# AUDIO2.net
KiCad netlist of a schematic drawn in Altium Designer
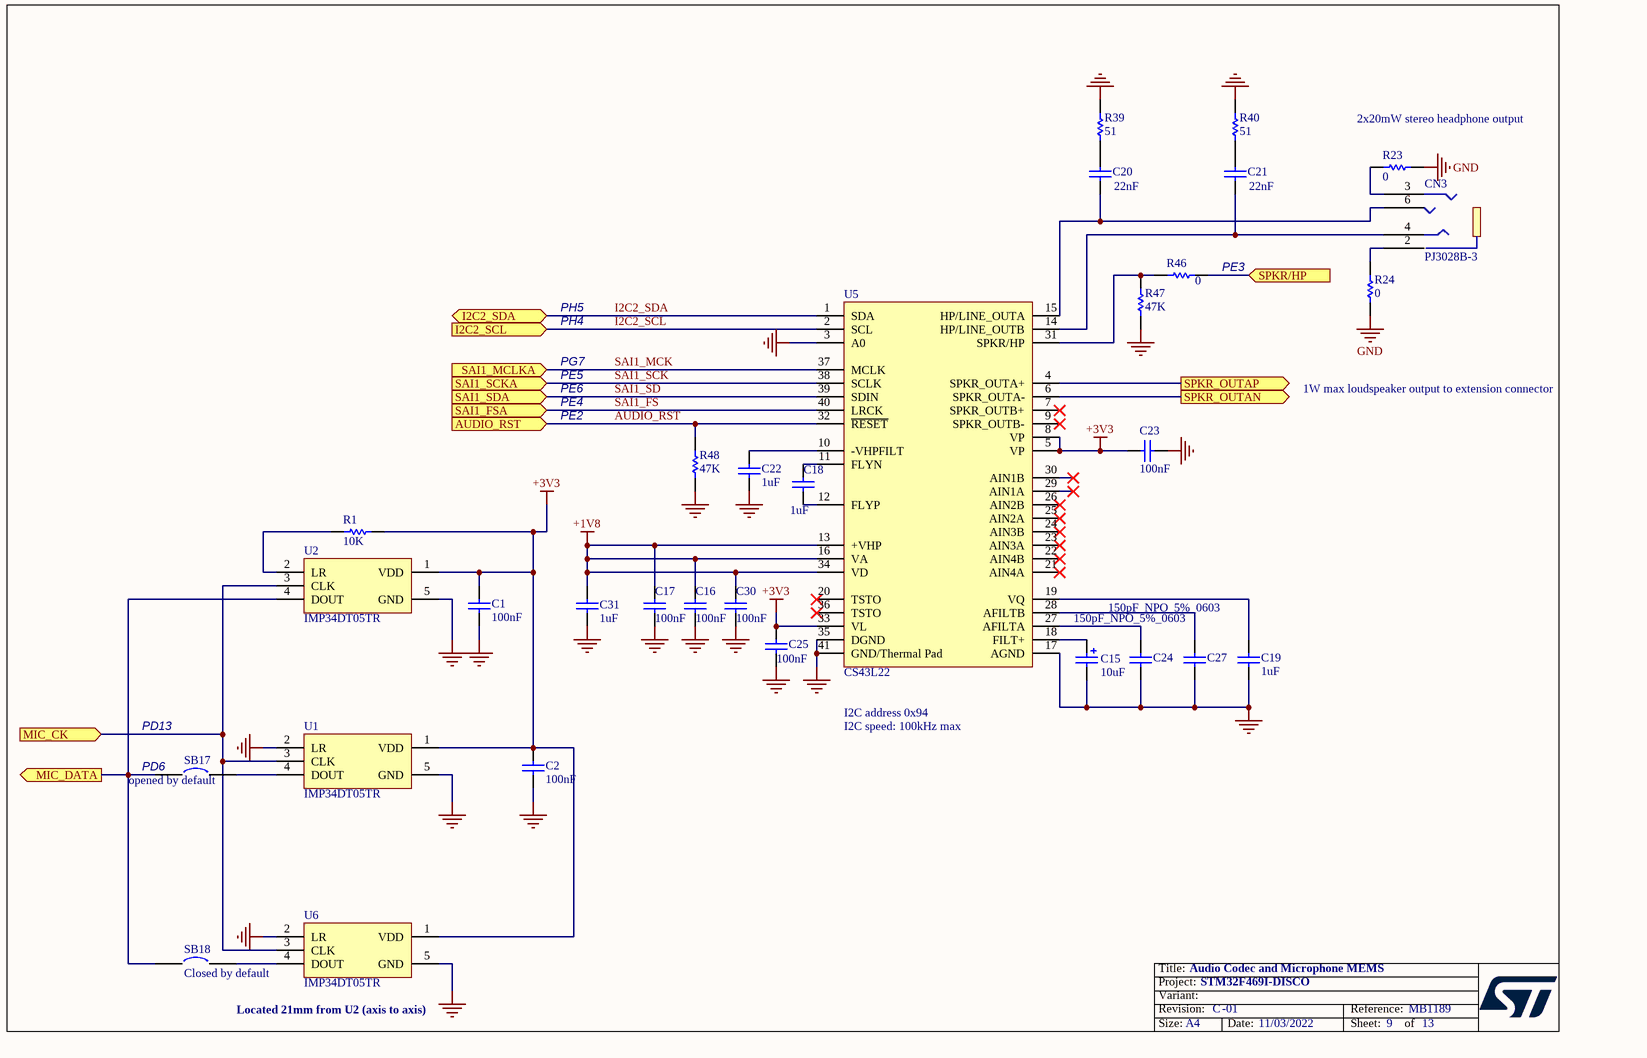
[diagram p0: AUDIO2.SchDoc]

(export (version "E")
  (design (tool "Eeschema 10.0.6"))
  (components
    (comp (ref "C1")
      (value "100nF")
      (footprint "0402C")
      (description "Capacitor")
      (fields (field (name "PUBLISHER") "Altium Limited"))
      (libsource (lib "Miscellaneous Devices") (part "Cap"))
    )
    (comp (ref "C2")
      (value "100nF")
      (footprint "0402C")
      (description "Capacitor")
      (fields (field (name "PUBLISHER") "Altium Limited"))
      (libsource (lib "Miscellaneous Devices") (part "Cap"))
    )
    (comp (ref "C15")
      (value "10uF")
      (footprint "CPOL_TAJ-A_1206_H180")
      (description "Capacitor, Tantalum, 10uF, 16V, 10%, 3Ohms, pkg Type_A (3216 metric), T=1.6mm")
      (libsource (lib "MB1189") (part "Cap_TAJA106K016R"))
    )
    (comp (ref "C16")
      (value "100nF")
      (footprint "0402C")
      (description "Capacitor")
      (fields (field (name "PUBLISHER") "Altium Limited"))
      (libsource (lib "Miscellaneous Devices") (part "CAP"))
    )
    (comp (ref "C17")
      (value "100nF")
      (footprint "0402C")
      (description "Capacitor")
      (fields (field (name "PUBLISHER") "Altium Limited"))
      (libsource (lib "Miscellaneous Devices") (part "CAP"))
    )
    (comp (ref "C18")
      (value "1uF")
      (footprint "0603C")
      (description "Capacitor")
      (fields (field (name "PUBLISHER") "Altium Limited"))
      (libsource (lib "Miscellaneous Devices") (part "CAP"))
    )
    (comp (ref "C19")
      (value "1uF")
      (footprint "0603C")
      (description "Capacitor")
      (fields (field (name "PUBLISHER") "Altium Limited"))
      (libsource (lib "Miscellaneous Devices") (part "CAP"))
    )
    (comp (ref "C20")
      (value "22nF")
      (footprint "0603C")
      (description "Capacitor,22nF,50V,X7R,10%,0603,YAGEO")
      (libsource (lib "MCD_TOOLS") (part "Cap_22nF_X7R_10%_0603"))
    )
    (comp (ref "C21")
      (value "22nF")
      (footprint "0603C")
      (description "Capacitor,22nF,50V,X7R,10%,0603,YAGEO")
      (libsource (lib "MCD_TOOLS") (part "Cap_22nF_X7R_10%_0603"))
    )
    (comp (ref "C22")
      (value "1uF")
      (footprint "0603C")
      (description "Capacitor")
      (fields (field (name "PUBLISHER") "Altium Limited"))
      (libsource (lib "Miscellaneous Devices") (part "CAP"))
    )
    (comp (ref "C23")
      (value "100nF")
      (footprint "0402C")
      (description "Capacitor")
      (fields (field (name "PUBLISHER") "Altium Limited"))
      (libsource (lib "Miscellaneous Devices") (part "CAP"))
    )
    (comp (ref "C24")
      (value "150pF_NPO_5%_0603")
      (footprint "0603C")
      (description "Capacitor,150pF,50V,NPO,5%,0603,YAGEO")
      (libsource (lib "MCD_TOOLS") (part "Cap_150pF_NPO_5%_0603"))
    )
    (comp (ref "C25")
      (value "100nF")
      (footprint "0402C")
      (description "Capacitor")
      (fields (field (name "PUBLISHER") "Altium Limited"))
      (libsource (lib "Miscellaneous Devices") (part "CAP"))
    )
    (comp (ref "C27")
      (value "150pF_NPO_5%_0603")
      (footprint "0603C")
      (description "Capacitor,150pF,50V,NPO,5%,0603,YAGEO")
      (libsource (lib "MCD_TOOLS") (part "Cap_150pF_NPO_5%_0603"))
    )
    (comp (ref "C30")
      (value "100nF")
      (footprint "0402C")
      (description "Capacitor")
      (fields (field (name "PUBLISHER") "Altium Limited"))
      (libsource (lib "Miscellaneous Devices") (part "CAP"))
    )
    (comp (ref "C31")
      (value "1uF")
      (footprint "0603C")
      (description "Capacitor")
      (fields (field (name "PUBLISHER") "Altium Limited"))
      (libsource (lib "Miscellaneous Devices") (part "CAP"))
    )
    (comp (ref "CN3") (value "PJ3028B-3") (footprint "PJ3028B") (libsource (lib "MB786") (part "PJ3028B-3")))
    (comp (ref "R1")
      (value "10K")
      (footprint "0603R")
      (description "Resistor")
      (libsource (lib "MCD_TOOLS") (part "Res_0_5%_0402"))
    )
    (comp (ref "R23")
      (value "0")
      (footprint "0603R")
      (description "Resistor")
      (fields (field (name "PUBLISHER") "Altium Limited"))
      (libsource (lib "") (part "Res1_1"))
    )
    (comp (ref "R24")
      (value "0")
      (footprint "0603R")
      (description "Resistor")
      (fields (field (name "PUBLISHER") "Altium Limited"))
      (libsource (lib "") (part "Res1_1"))
    )
    (comp (ref "R39")
      (value "51")
      (footprint "0402R")
      (description "Resistor")
      (libsource (lib "MCD_TOOLS") (part "Res_51_1%_0402"))
    )
    (comp (ref "R40")
      (value "51")
      (footprint "0402R")
      (description "Resistor")
      (libsource (lib "MCD_TOOLS") (part "Res_51_1%_0402"))
    )
    (comp (ref "R46")
      (value "0")
      (footprint "0603R")
      (description "Resistor")
      (fields (field (name "PUBLISHER") "Altium Limited"))
      (libsource (lib "Miscellaneous Devices") (part "Res1"))
    )
    (comp (ref "R47")
      (value "47K")
      (footprint "0603R")
      (description "Resistor")
      (fields (field (name "PUBLISHER") "Altium Limited"))
      (libsource (lib "Miscellaneous Devices") (part "Res1"))
    )
    (comp (ref "R48")
      (value "47K")
      (footprint "0603R")
      (description "Resistor")
      (fields (field (name "PUBLISHER") "Altium Limited"))
      (libsource (lib "Miscellaneous Devices") (part "Res1"))
    )
    (comp (ref "SB17")
      (value "opened by default")
      (footprint "SB_0603")
      (description "Circuit Breaker")
      (fields (field (name "PUBLISHER") "Altium Limited"))
      (libsource (lib "MB1189") (part "Circuit Breaker"))
    )
    (comp (ref "SB18")
      (value "Closed by default")
      (footprint "SB_0603")
      (description "Circuit Breaker")
      (fields (field (name "PUBLISHER") "Altium Limited"))
      (libsource (lib "MB1189") (part "Circuit Breaker"))
    )
    (comp (ref "U1")
      (value "IMP34DT05TR")
      (footprint "MIC_HCLGA_3X4X1_4LD_")
      (description "MEMS audio sensor omnidirectional digital microphone for industrial applications")
      (fields (field (name "PUBLISHER") "Altium Limited"))
      (libsource (lib "MB1189") (part "IMP34DT05TR"))
    )
    (comp (ref "U2")
      (value "IMP34DT05TR")
      (footprint "MIC_HCLGA_3X4X1_4LD_")
      (description "MEMS audio sensor omnidirectional digital microphone for industrial applications")
      (fields (field (name "PUBLISHER") "Altium Limited"))
      (libsource (lib "MB1189") (part "IMP34DT05TR"))
    )
    (comp (ref "U5")
      (value "CS43L22")
      (footprint "QFN40_0R5_6X6")
      (description "Low Power, Stereo DAC w/Headphone & Speaker Amps")
      (libsource (lib "MCD_TOOLS") (part "CS43L22"))
    )
    (comp (ref "U6")
      (value "IMP34DT05TR")
      (footprint "MIC_HCLGA_3X4X1_4LD_")
      (description "MEMS audio sensor omnidirectional digital microphone for industrial applications")
      (fields (field (name "PUBLISHER") "Altium Limited"))
      (libsource (lib "MB1189") (part "IMP34DT05TR"))
    )
  )
  (nets
    (net (code "1") (name "+1V8") (class "Default")
      (node (ref "C16") (pin "1") (pinfunction "1_1") (pintype "passive"))
      (node (ref "C17") (pin "1") (pinfunction "1_1") (pintype "passive"))
      (node (ref "C30") (pin "1") (pinfunction "1_1") (pintype "passive"))
      (node (ref "C31") (pin "1") (pinfunction "1_1") (pintype "passive"))
      (node (ref "U5") (pin "13") (pinfunction "+VHP_13") (pintype "passive"))
      (node (ref "U5") (pin "16") (pinfunction "VA_16") (pintype "passive"))
      (node (ref "U5") (pin "34") (pinfunction "VD_34") (pintype "passive"))
    )
    (net (code "2") (name "+3V3") (class "Default")
      (node (ref "C1") (pin "2") (pinfunction "2_2") (pintype "passive"))
      (node (ref "C2") (pin "2") (pinfunction "2_2") (pintype "passive"))
      (node (ref "C23") (pin "2") (pinfunction "2_2") (pintype "passive"))
      (node (ref "C25") (pin "1") (pinfunction "1_1") (pintype "passive"))
      (node (ref "R1") (pin "2") (pinfunction "2_2") (pintype "passive"))
      (node (ref "U1") (pin "1") (pinfunction "VDD_1") (pintype "passive"))
      (node (ref "U2") (pin "1") (pinfunction "VDD_1") (pintype "passive"))
      (node (ref "U5") (pin "33") (pinfunction "VL_33") (pintype "passive"))
      (node (ref "U5") (pin "5") (pinfunction "VP_5") (pintype "passive"))
      (node (ref "U5") (pin "8") (pinfunction "VP_8") (pintype "passive"))
      (node (ref "U6") (pin "1") (pinfunction "VDD_1") (pintype "passive"))
    )
    (net (code "3") (name "/AUDIO_RST") (class "Default")
      (node (ref "R48") (pin "2") (pinfunction "2_2") (pintype "passive"))
      (node (ref "U5") (pin "32") (pinfunction "~{RESET}_32") (pintype "passive"))
    )
    (net (code "4") (name "/I2C2_SCL") (class "Default")
      (node (ref "U5") (pin "2") (pinfunction "SCL_2") (pintype "passive"))
    )
    (net (code "5") (name "/I2C2_SDA") (class "Default")
      (node (ref "U5") (pin "1") (pinfunction "SDA_1") (pintype "passive"))
    )
    (net (code "6") (name "/MIC_CK") (class "Default")
      (node (ref "U1") (pin "3") (pinfunction "CLK_3") (pintype "passive"))
      (node (ref "U2") (pin "3") (pinfunction "CLK_3") (pintype "passive"))
      (node (ref "U6") (pin "3") (pinfunction "CLK_3") (pintype "passive"))
    )
    (net (code "7") (name "/MIC_DATA") (class "Default")
      (node (ref "SB17") (pin "2") (pinfunction "2_2") (pintype "passive"))
      (node (ref "SB18") (pin "2") (pinfunction "2_2") (pintype "passive"))
      (node (ref "U2") (pin "4") (pinfunction "DOUT_4") (pintype "passive"))
    )
    (net (code "8") (name "/SAI1_FS") (class "Default")
      (node (ref "U5") (pin "40") (pinfunction "LRCK_40") (pintype "passive"))
    )
    (net (code "9") (name "/SAI1_MCK") (class "Default")
      (node (ref "U5") (pin "37") (pinfunction "MCLK_37") (pintype "passive"))
    )
    (net (code "10") (name "/SAI1_SCK") (class "Default")
      (node (ref "U5") (pin "38") (pinfunction "SCLK_38") (pintype "passive"))
    )
    (net (code "11") (name "/SAI1_SD") (class "Default")
      (node (ref "U5") (pin "39") (pinfunction "SDIN_39") (pintype "passive"))
    )
    (net (code "12") (name "/SPKR_OUTAN") (class "Default")
      (node (ref "U5") (pin "6") (pinfunction "SPKR_OUTA-_6") (pintype "passive"))
    )
    (net (code "13") (name "/SPKR_OUTAP") (class "Default")
      (node (ref "U5") (pin "4") (pinfunction "SPKR_OUTA+_4") (pintype "passive"))
    )
    (net (code "14") (name "/SPKR{slash}HP") (class "Default")
      (node (ref "R46") (pin "2") (pinfunction "2_2") (pintype "passive"))
    )
    (net (code "15") (name "GND") (class "Default")
      (node (ref "C1") (pin "1") (pinfunction "1_1") (pintype "passive"))
      (node (ref "C15") (pin "2") (pinfunction "2_2") (pintype "passive"))
      (node (ref "C16") (pin "2") (pinfunction "2_2") (pintype "passive"))
      (node (ref "C17") (pin "2") (pinfunction "2_2") (pintype "passive"))
      (node (ref "C19") (pin "1") (pinfunction "1_1") (pintype "passive"))
      (node (ref "C2") (pin "1") (pinfunction "1_1") (pintype "passive"))
      (node (ref "C22") (pin "1") (pinfunction "1_1") (pintype "passive"))
      (node (ref "C23") (pin "1") (pinfunction "1_1") (pintype "passive"))
      (node (ref "C24") (pin "1") (pinfunction "1_1") (pintype "passive"))
      (node (ref "C25") (pin "2") (pinfunction "2_2") (pintype "passive"))
      (node (ref "C27") (pin "1") (pinfunction "1_1") (pintype "passive"))
      (node (ref "C30") (pin "2") (pinfunction "2_2") (pintype "passive"))
      (node (ref "C31") (pin "2") (pinfunction "2_2") (pintype "passive"))
      (node (ref "R23") (pin "2") (pinfunction "2_2") (pintype "passive"))
      (node (ref "R24") (pin "2") (pinfunction "2_2") (pintype "passive"))
      (node (ref "R39") (pin "2") (pinfunction "2_2") (pintype "passive"))
      (node (ref "R40") (pin "2") (pinfunction "2_2") (pintype "passive"))
      (node (ref "R47") (pin "2") (pinfunction "2_2") (pintype "passive"))
      (node (ref "R48") (pin "1") (pinfunction "1_1") (pintype "passive"))
      (node (ref "U1") (pin "2") (pinfunction "LR_2") (pintype "passive"))
      (node (ref "U1") (pin "5") (pinfunction "GND_5") (pintype "passive"))
      (node (ref "U2") (pin "5") (pinfunction "GND_5") (pintype "passive"))
      (node (ref "U5") (pin "17") (pinfunction "AGND_17") (pintype "passive"))
      (node (ref "U5") (pin "3") (pinfunction "A0_3") (pintype "passive"))
      (node (ref "U5") (pin "35") (pinfunction "DGND_35") (pintype "passive"))
      (node (ref "U5") (pin "41") (pinfunction "GND/Thermal_Pad_41") (pintype "passive"))
      (node (ref "U6") (pin "2") (pinfunction "LR_2") (pintype "passive"))
      (node (ref "U6") (pin "5") (pinfunction "GND_5") (pintype "passive"))
    )
    (net (code "16") (name "Net-(C20-Pad2)") (class "Default")
      (node (ref "C20") (pin "2") (pinfunction "2_2") (pintype "passive"))
      (node (ref "R39") (pin "1") (pinfunction "1_1") (pintype "passive"))
    )
    (net (code "17") (name "Net-(C21-Pad2)") (class "Default")
      (node (ref "C21") (pin "2") (pinfunction "2_2") (pintype "passive"))
      (node (ref "R40") (pin "1") (pinfunction "1_1") (pintype "passive"))
    )
    (net (code "18") (name "Net-(CN3-Pad2)") (class "Default")
      (node (ref "CN3") (pin "2") (pintype "passive"))
      (node (ref "R24") (pin "1") (pinfunction "1_1") (pintype "passive"))
    )
    (net (code "19") (name "Net-(CN3-Pad3)") (class "Default")
      (node (ref "CN3") (pin "3") (pintype "passive"))
      (node (ref "R23") (pin "1") (pinfunction "1_1") (pintype "passive"))
    )
    (net (code "20") (name "Net-(U1-DOUT)") (class "Default")
      (node (ref "SB17") (pin "1") (pinfunction "1_1") (pintype "passive"))
      (node (ref "U1") (pin "4") (pinfunction "DOUT_4") (pintype "passive"))
    )
    (net (code "21") (name "Net-(U2-LR)") (class "Default")
      (node (ref "R1") (pin "1") (pinfunction "1_1") (pintype "passive"))
      (node (ref "U2") (pin "2") (pinfunction "LR_2") (pintype "passive"))
    )
    (net (code "22") (name "Net-(U5--VHPFILT)") (class "Default")
      (node (ref "C22") (pin "2") (pinfunction "2_2") (pintype "passive"))
      (node (ref "U5") (pin "10") (pinfunction "-VHPFILT_10") (pintype "passive"))
    )
    (net (code "23") (name "Net-(U5-AFILTA)") (class "Default")
      (node (ref "C24") (pin "2") (pinfunction "2_2") (pintype "passive"))
      (node (ref "U5") (pin "27") (pinfunction "AFILTA_27") (pintype "passive"))
    )
    (net (code "24") (name "Net-(U5-AFILTB)") (class "Default")
      (node (ref "C27") (pin "2") (pinfunction "2_2") (pintype "passive"))
      (node (ref "U5") (pin "28") (pinfunction "AFILTB_28") (pintype "passive"))
    )
    (net (code "25") (name "Net-(U5-FILT+)") (class "Default")
      (node (ref "C15") (pin "1") (pinfunction "1_1") (pintype "passive"))
      (node (ref "U5") (pin "18") (pinfunction "FILT+_18") (pintype "passive"))
    )
    (net (code "26") (name "Net-(U5-FLYN)") (class "Default")
      (node (ref "C18") (pin "1") (pinfunction "1_1") (pintype "passive"))
      (node (ref "U5") (pin "11") (pinfunction "FLYN_11") (pintype "passive"))
    )
    (net (code "27") (name "Net-(U5-FLYP)") (class "Default")
      (node (ref "C18") (pin "2") (pinfunction "2_2") (pintype "passive"))
      (node (ref "U5") (pin "12") (pinfunction "FLYP_12") (pintype "passive"))
    )
    (net (code "28") (name "Net-(U5-HP{slash}LINE_OUTA)") (class "Default")
      (node (ref "C20") (pin "1") (pinfunction "1_1") (pintype "passive"))
      (node (ref "CN3") (pin "6") (pintype "passive"))
      (node (ref "U5") (pin "15") (pinfunction "HP/LINE_OUTA_15") (pintype "passive"))
    )
    (net (code "29") (name "Net-(U5-HP{slash}LINE_OUTB)") (class "Default")
      (node (ref "C21") (pin "1") (pinfunction "1_1") (pintype "passive"))
      (node (ref "CN3") (pin "4") (pintype "passive"))
      (node (ref "U5") (pin "14") (pinfunction "HP/LINE_OUTB_14") (pintype "passive"))
    )
    (net (code "30") (name "Net-(U5-SPKR{slash}HP)") (class "Default")
      (node (ref "R46") (pin "1") (pinfunction "1_1") (pintype "passive"))
      (node (ref "R47") (pin "1") (pinfunction "1_1") (pintype "passive"))
      (node (ref "U5") (pin "31") (pinfunction "SPKR/HP_31") (pintype "passive"))
    )
    (net (code "31") (name "Net-(U5-VQ)") (class "Default")
      (node (ref "C19") (pin "2") (pinfunction "2_2") (pintype "passive"))
      (node (ref "U5") (pin "19") (pinfunction "VQ_19") (pintype "passive"))
    )
    (net (code "32") (name "Net-(U6-DOUT)") (class "Default")
      (node (ref "SB18") (pin "1") (pinfunction "1_1") (pintype "passive"))
      (node (ref "U6") (pin "4") (pinfunction "DOUT_4") (pintype "passive"))
    )
    (net (code "33") (name "unconnected-(U5-AIN1A-Pad29)") (class "Default")
      (node (ref "U5") (pin "29") (pinfunction "AIN1A_29") (pintype "passive+no_connect"))
    )
    (net (code "34") (name "unconnected-(U5-AIN1B-Pad30)") (class "Default")
      (node (ref "U5") (pin "30") (pinfunction "AIN1B_30") (pintype "passive+no_connect"))
    )
    (net (code "35") (name "unconnected-(U5-AIN2A-Pad25)") (class "Default")
      (node (ref "U5") (pin "25") (pinfunction "AIN2A_25") (pintype "passive+no_connect"))
    )
    (net (code "36") (name "unconnected-(U5-AIN2B-Pad26)") (class "Default")
      (node (ref "U5") (pin "26") (pinfunction "AIN2B_26") (pintype "passive+no_connect"))
    )
    (net (code "37") (name "unconnected-(U5-AIN3A-Pad23)") (class "Default")
      (node (ref "U5") (pin "23") (pinfunction "AIN3A_23") (pintype "passive+no_connect"))
    )
    (net (code "38") (name "unconnected-(U5-AIN3B-Pad24)") (class "Default")
      (node (ref "U5") (pin "24") (pinfunction "AIN3B_24") (pintype "passive+no_connect"))
    )
    (net (code "39") (name "unconnected-(U5-AIN4A-Pad21)") (class "Default")
      (node (ref "U5") (pin "21") (pinfunction "AIN4A_21") (pintype "passive+no_connect"))
    )
    (net (code "40") (name "unconnected-(U5-AIN4B-Pad22)") (class "Default")
      (node (ref "U5") (pin "22") (pinfunction "AIN4B_22") (pintype "passive+no_connect"))
    )
    (net (code "41") (name "unconnected-(U5-SPKR_OUTB+-Pad7)") (class "Default")
      (node (ref "U5") (pin "7") (pinfunction "SPKR_OUTB+_7") (pintype "passive+no_connect"))
    )
    (net (code "42") (name "unconnected-(U5-SPKR_OUTB--Pad9)") (class "Default")
      (node (ref "U5") (pin "9") (pinfunction "SPKR_OUTB-_9") (pintype "passive+no_connect"))
    )
    (net (code "43") (name "unconnected-(U5-TSTO-Pad20)") (class "Default")
      (node (ref "U5") (pin "20") (pinfunction "TSTO_20") (pintype "passive+no_connect"))
    )
    (net (code "44") (name "unconnected-(U5-TSTO-Pad36)") (class "Default")
      (node (ref "U5") (pin "36") (pinfunction "TSTO_36") (pintype "passive+no_connect"))
    )
  )
)
